# flight_controller_initial1.net
KiCad netlist of a schematic drawn in EAGLE
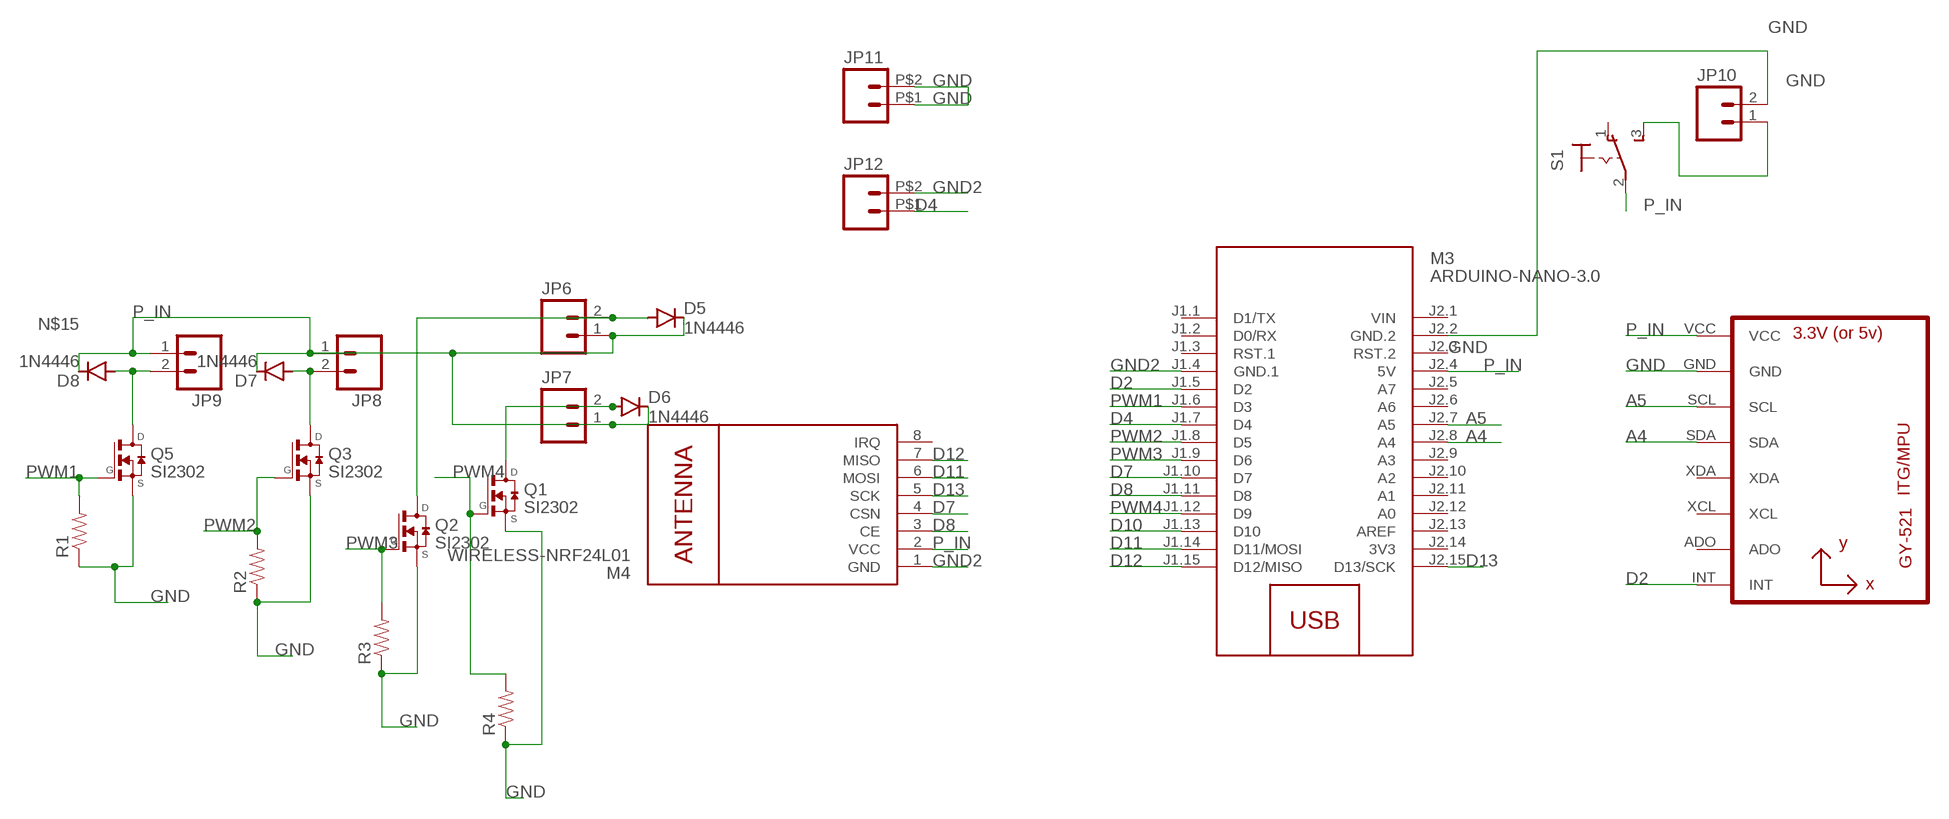
[diagram p0: schematic, sheet 1]

(export (version "E")
  (design (tool "Eeschema 10.0.6"))
  (components
    (comp (ref "D5")
      (value "1N4446")
      (footprint "eagle-import:DO35-10")
      (libsource (lib "eagle-import") (part "1N4446"))
    )
    (comp (ref "D6")
      (value "1N4446")
      (footprint "eagle-import:DO35-10")
      (libsource (lib "eagle-import") (part "1N4446"))
    )
    (comp (ref "D7")
      (value "1N4446")
      (footprint "eagle-import:DO35-10")
      (libsource (lib "eagle-import") (part "1N4446"))
    )
    (comp (ref "D8")
      (value "1N4446")
      (footprint "eagle-import:DO35-10")
      (libsource (lib "eagle-import") (part "1N4446"))
    )
    (comp (ref "JP6")
      (value "M021X02_NO_SILK")
      (footprint "eagle-import:1X02_NO_SILK")
      (libsource (lib "eagle-import") (part "M021X02_NO_SILK"))
    )
    (comp (ref "JP7")
      (value "M021X02_NO_SILK")
      (footprint "eagle-import:1X02_NO_SILK")
      (libsource (lib "eagle-import") (part "M021X02_NO_SILK"))
    )
    (comp (ref "JP8")
      (value "M021X02_NO_SILK")
      (footprint "eagle-import:1X02_NO_SILK")
      (libsource (lib "eagle-import") (part "M021X02_NO_SILK"))
    )
    (comp (ref "JP9")
      (value "M021X02_NO_SILK")
      (footprint "eagle-import:1X02_NO_SILK")
      (libsource (lib "eagle-import") (part "M021X02_NO_SILK"))
    )
    (comp (ref "JP10")
      (value "M02PTH")
      (footprint "eagle-import:1X02")
      (libsource (lib "eagle-import") (part "M02PTH"))
    )
    (comp (ref "JP11")
      (value "M02PTH2")
      (footprint "eagle-import:1X02_BIG")
      (libsource (lib "eagle-import") (part "M02PTH2"))
    )
    (comp (ref "JP12")
      (value "M02PTH2")
      (footprint "eagle-import:1X02_BIG")
      (libsource (lib "eagle-import") (part "M02PTH2"))
    )
    (comp (ref "M3")
      (value "ARDUINO-NANO-3.0")
      (footprint "eagle-import:ARDUINO-NANO-3.0")
      (libsource (lib "eagle-import") (part "ARDUINO-NANO-3.0"))
    )
    (comp (ref "M4")
      (value "WIRELESS-NRF24L01")
      (footprint "eagle-import:WIRELESS-NRF24L01")
      (libsource (lib "eagle-import") (part "WIRELESS-NRF24L01"))
    )
    (comp (ref "Q1")
      (value "SI2302")
      (footprint "eagle-import:SOT23")
      (libsource (lib "eagle-import") (part "SI2302"))
    )
    (comp (ref "Q2")
      (value "SI2302")
      (footprint "eagle-import:SOT23")
      (libsource (lib "eagle-import") (part "SI2302"))
    )
    (comp (ref "Q3")
      (value "SI2302")
      (footprint "eagle-import:SOT23")
      (libsource (lib "eagle-import") (part "SI2302"))
    )
    (comp (ref "Q5")
      (value "SI2302")
      (footprint "eagle-import:SOT23")
      (libsource (lib "eagle-import") (part "SI2302"))
    )
    (comp (ref "R1")
      (value "RESISTORAXIAL-0.3")
      (footprint "eagle-import:AXIAL-0.3")
      (libsource (lib "eagle-import") (part "RESISTORAXIAL-0.3"))
    )
    (comp (ref "R2")
      (value "RESISTORAXIAL-0.3")
      (footprint "eagle-import:AXIAL-0.3")
      (libsource (lib "eagle-import") (part "RESISTORAXIAL-0.3"))
    )
    (comp (ref "R3")
      (value "RESISTORAXIAL-0.3")
      (footprint "eagle-import:AXIAL-0.3")
      (libsource (lib "eagle-import") (part "RESISTORAXIAL-0.3"))
    )
    (comp (ref "R4")
      (value "RESISTORAXIAL-0.3")
      (footprint "eagle-import:AXIAL-0.3")
      (libsource (lib "eagle-import") (part "RESISTORAXIAL-0.3"))
    )
    (comp (ref "S1")
      (value "M9040P")
      (footprint "eagle-import:M9040P")
      (libsource (lib "eagle-import") (part "M9040P"))
    )
    (comp (ref "U2")
      (value "GY-521MPU6050")
      (footprint "eagle-import:GY-521")
      (libsource (lib "eagle-import") (part "GY-521MPU6050"))
    )
  )
  (nets
    (net (code "1") (name "/3V3") (class "Default")
      (node (ref "M3") (pin "J2.14") (pinfunction "3V3_J2.14") (pintype "power_in"))
    )
    (net (code "2") (name "/A4") (class "Default")
      (node (ref "M3") (pin "J2.8") (pinfunction "A4_J2.8") (pintype "bidirectional"))
      (node (ref "U2") (pin "SDA") (pinfunction "SDA_SDA") (pintype "bidirectional"))
    )
    (net (code "3") (name "/A5") (class "Default")
      (node (ref "M3") (pin "J2.7") (pinfunction "A5_J2.7") (pintype "bidirectional"))
      (node (ref "U2") (pin "SCL") (pinfunction "SCL_SCL") (pintype "bidirectional"))
    )
    (net (code "4") (name "/D2") (class "Default")
      (node (ref "M3") (pin "J1.5") (pinfunction "D2_J1.5") (pintype "bidirectional"))
      (node (ref "U2") (pin "INT") (pinfunction "INT_INT") (pintype "bidirectional"))
    )
    (net (code "5") (name "/D4") (class "Default")
      (node (ref "JP12") (pin "P$1") (pinfunction "1_P$1") (pintype "passive"))
      (node (ref "M3") (pin "J1.7") (pinfunction "D4_J1.7") (pintype "bidirectional"))
    )
    (net (code "6") (name "/D7") (class "Default")
      (node (ref "M3") (pin "J1.10") (pinfunction "D7_J1.10") (pintype "bidirectional"))
      (node (ref "M4") (pin "4") (pinfunction "CSN_4") (pintype "bidirectional"))
    )
    (net (code "7") (name "/D8") (class "Default")
      (node (ref "M3") (pin "J1.11") (pinfunction "D8_J1.11") (pintype "bidirectional"))
      (node (ref "M4") (pin "3") (pinfunction "CE_3") (pintype "bidirectional"))
    )
    (net (code "8") (name "/D10") (class "Default")
      (node (ref "M3") (pin "J1.13") (pinfunction "D10_J1.13") (pintype "bidirectional"))
    )
    (net (code "9") (name "/D11") (class "Default")
      (node (ref "M3") (pin "J1.14") (pinfunction "D11/MOSI_J1.14") (pintype "bidirectional"))
      (node (ref "M4") (pin "6") (pinfunction "MOSI_6") (pintype "bidirectional"))
    )
    (net (code "10") (name "/D12") (class "Default")
      (node (ref "M3") (pin "J1.15") (pinfunction "D12/MISO_J1.15") (pintype "bidirectional"))
      (node (ref "M4") (pin "7") (pinfunction "MISO_7") (pintype "bidirectional"))
    )
    (net (code "11") (name "/D13") (class "Default")
      (node (ref "M3") (pin "J2.15") (pinfunction "D13/SCK_J2.15") (pintype "bidirectional"))
      (node (ref "M4") (pin "5") (pinfunction "SCK_5") (pintype "bidirectional"))
    )
    (net (code "12") (name "/GND") (class "Default")
      (node (ref "JP10") (pin "2") (pinfunction "2_2") (pintype "passive"))
      (node (ref "JP11") (pin "P$1") (pinfunction "1_P$1") (pintype "passive"))
      (node (ref "JP11") (pin "P$2") (pinfunction "2_P$2") (pintype "passive"))
      (node (ref "M3") (pin "J2.2") (pinfunction "GND.2_J2.2") (pintype "power_in"))
      (node (ref "Q1") (pin "2") (pinfunction "S_2") (pintype "passive"))
      (node (ref "Q2") (pin "2") (pinfunction "S_2") (pintype "passive"))
      (node (ref "Q3") (pin "2") (pinfunction "S_2") (pintype "passive"))
      (node (ref "Q5") (pin "2") (pinfunction "S_2") (pintype "passive"))
      (node (ref "R1") (pin "P$1") (pinfunction "1_P$1") (pintype "passive"))
      (node (ref "R2") (pin "P$1") (pinfunction "1_P$1") (pintype "passive"))
      (node (ref "R3") (pin "P$1") (pinfunction "1_P$1") (pintype "passive"))
      (node (ref "R4") (pin "P$1") (pinfunction "1_P$1") (pintype "passive"))
      (node (ref "U2") (pin "GND") (pinfunction "GND_GND") (pintype "bidirectional"))
    )
    (net (code "13") (name "/GND2") (class "Default")
      (node (ref "JP12") (pin "P$2") (pinfunction "2_P$2") (pintype "passive"))
      (node (ref "M3") (pin "J1.4") (pinfunction "GND.1_J1.4") (pintype "power_in"))
      (node (ref "M4") (pin "1") (pinfunction "GND_1") (pintype "power_in"))
    )
    (net (code "14") (name "/N$15") (class "Default")
      (node (ref "D8") (pin "A") (pinfunction "A_A") (pintype "passive"))
      (node (ref "JP9") (pin "2") (pinfunction "2_2") (pintype "passive"))
      (node (ref "Q5") (pin "3") (pinfunction "D_3") (pintype "passive"))
    )
    (net (code "15") (name "/PWM1") (class "Default")
      (node (ref "M3") (pin "J1.6") (pinfunction "D3_J1.6") (pintype "bidirectional"))
      (node (ref "Q5") (pin "1") (pinfunction "G_1") (pintype "passive"))
      (node (ref "R1") (pin "P$2") (pinfunction "2_P$2") (pintype "passive"))
    )
    (net (code "16") (name "/PWM2") (class "Default")
      (node (ref "M3") (pin "J1.8") (pinfunction "D5_J1.8") (pintype "bidirectional"))
      (node (ref "Q3") (pin "1") (pinfunction "G_1") (pintype "passive"))
      (node (ref "R2") (pin "P$2") (pinfunction "2_P$2") (pintype "passive"))
    )
    (net (code "17") (name "/PWM3") (class "Default")
      (node (ref "M3") (pin "J1.9") (pinfunction "D6_J1.9") (pintype "bidirectional"))
      (node (ref "Q2") (pin "1") (pinfunction "G_1") (pintype "passive"))
      (node (ref "R3") (pin "P$2") (pinfunction "2_P$2") (pintype "passive"))
    )
    (net (code "18") (name "/PWM4") (class "Default")
      (node (ref "M3") (pin "J1.12") (pinfunction "D9_J1.12") (pintype "bidirectional"))
      (node (ref "Q1") (pin "1") (pinfunction "G_1") (pintype "passive"))
      (node (ref "R4") (pin "P$2") (pinfunction "2_P$2") (pintype "passive"))
    )
    (net (code "19") (name "/P_IN") (class "Default")
      (node (ref "D5") (pin "C") (pinfunction "C_C") (pintype "passive"))
      (node (ref "D6") (pin "C") (pinfunction "C_C") (pintype "passive"))
      (node (ref "D7") (pin "C") (pinfunction "C_C") (pintype "passive"))
      (node (ref "D8") (pin "C") (pinfunction "C_C") (pintype "passive"))
      (node (ref "JP6") (pin "1") (pinfunction "1_1") (pintype "passive"))
      (node (ref "JP7") (pin "1") (pinfunction "1_1") (pintype "passive"))
      (node (ref "JP8") (pin "1") (pinfunction "1_1") (pintype "passive"))
      (node (ref "JP9") (pin "1") (pinfunction "1_1") (pintype "passive"))
      (node (ref "M3") (pin "J2.4") (pinfunction "5V_J2.4") (pintype "power_in"))
      (node (ref "M4") (pin "2") (pinfunction "VCC_2") (pintype "power_in"))
      (node (ref "S1") (pin "2") (pinfunction "P_2") (pintype "passive"))
      (node (ref "U2") (pin "VCC") (pinfunction "VCC_VCC") (pintype "bidirectional"))
    )
    (net (code "20") (name "/VIN") (class "Default")
      (node (ref "M3") (pin "J2.1") (pinfunction "VIN_J2.1") (pintype "power_in"))
    )
    (net (code "21") (name "Net-(Q1-D)") (class "Default")
      (node (ref "D6") (pin "A") (pinfunction "A_A") (pintype "passive"))
      (node (ref "JP7") (pin "2") (pinfunction "2_2") (pintype "passive"))
      (node (ref "Q1") (pin "3") (pinfunction "D_3") (pintype "passive"))
    )
    (net (code "22") (name "Net-(Q2-D)") (class "Default")
      (node (ref "D5") (pin "A") (pinfunction "A_A") (pintype "passive"))
      (node (ref "JP6") (pin "2") (pinfunction "2_2") (pintype "passive"))
      (node (ref "Q2") (pin "3") (pinfunction "D_3") (pintype "passive"))
    )
    (net (code "23") (name "Net-(Q3-D)") (class "Default")
      (node (ref "D7") (pin "A") (pinfunction "A_A") (pintype "passive"))
      (node (ref "JP8") (pin "2") (pinfunction "2_2") (pintype "passive"))
      (node (ref "Q3") (pin "3") (pinfunction "D_3") (pintype "passive"))
    )
    (net (code "24") (name "Net-(S1-S)") (class "Default")
      (node (ref "JP10") (pin "1") (pinfunction "1_1") (pintype "passive"))
      (node (ref "S1") (pin "3") (pinfunction "S_3") (pintype "passive"))
    )
    (net (code "25") (name "unconnected-(M3-A0-PadJ2.12)") (class "Default")
      (node (ref "M3") (pin "J2.12") (pinfunction "A0_J2.12") (pintype "bidirectional"))
    )
    (net (code "26") (name "unconnected-(M3-A1-PadJ2.11)") (class "Default")
      (node (ref "M3") (pin "J2.11") (pinfunction "A1_J2.11") (pintype "bidirectional"))
    )
    (net (code "27") (name "unconnected-(M3-A2-PadJ2.10)") (class "Default")
      (node (ref "M3") (pin "J2.10") (pinfunction "A2_J2.10") (pintype "bidirectional"))
    )
    (net (code "28") (name "unconnected-(M3-A3-PadJ2.9)") (class "Default")
      (node (ref "M3") (pin "J2.9") (pinfunction "A3_J2.9") (pintype "bidirectional"))
    )
    (net (code "29") (name "unconnected-(M3-A6-PadJ2.6)") (class "Default")
      (node (ref "M3") (pin "J2.6") (pinfunction "A6_J2.6") (pintype "bidirectional"))
    )
    (net (code "30") (name "unconnected-(M3-A7-PadJ2.5)") (class "Default")
      (node (ref "M3") (pin "J2.5") (pinfunction "A7_J2.5") (pintype "bidirectional"))
    )
    (net (code "31") (name "unconnected-(M3-AREF-PadJ2.13)") (class "Default")
      (node (ref "M3") (pin "J2.13") (pinfunction "AREF_J2.13") (pintype "bidirectional"))
    )
    (net (code "32") (name "unconnected-(M3-D0{slash}RX-PadJ1.2)") (class "Default")
      (node (ref "M3") (pin "J1.2") (pinfunction "D0/RX_J1.2") (pintype "bidirectional"))
    )
    (net (code "33") (name "unconnected-(M3-D1{slash}TX-PadJ1.1)") (class "Default")
      (node (ref "M3") (pin "J1.1") (pinfunction "D1/TX_J1.1") (pintype "bidirectional"))
    )
    (net (code "34") (name "unconnected-(M3-RST.1-PadJ1.3)") (class "Default")
      (node (ref "M3") (pin "J1.3") (pinfunction "RST.1_J1.3") (pintype "bidirectional"))
    )
    (net (code "35") (name "unconnected-(M3-RST.2-PadJ2.3)") (class "Default")
      (node (ref "M3") (pin "J2.3") (pinfunction "RST.2_J2.3") (pintype "bidirectional"))
    )
    (net (code "36") (name "unconnected-(M4-IRQ-Pad8)") (class "Default")
      (node (ref "M4") (pin "8") (pinfunction "IRQ_8") (pintype "bidirectional"))
    )
    (net (code "37") (name "unconnected-(S1-O-Pad1)") (class "Default")
      (node (ref "S1") (pin "1") (pinfunction "O_1") (pintype "passive"))
    )
    (net (code "38") (name "unconnected-(U2-PadADO)") (class "Default")
      (node (ref "U2") (pin "ADO") (pinfunction "ADO_ADO") (pintype "bidirectional"))
    )
    (net (code "39") (name "unconnected-(U2-PadXCL)") (class "Default")
      (node (ref "U2") (pin "XCL") (pinfunction "XCL_XCL") (pintype "bidirectional"))
    )
    (net (code "40") (name "unconnected-(U2-PadXDA)") (class "Default")
      (node (ref "U2") (pin "XDA") (pinfunction "XDA_XDA") (pintype "bidirectional"))
    )
  )
)
